# AD_DA.net
KiCad netlist of a schematic drawn in Altium Designer
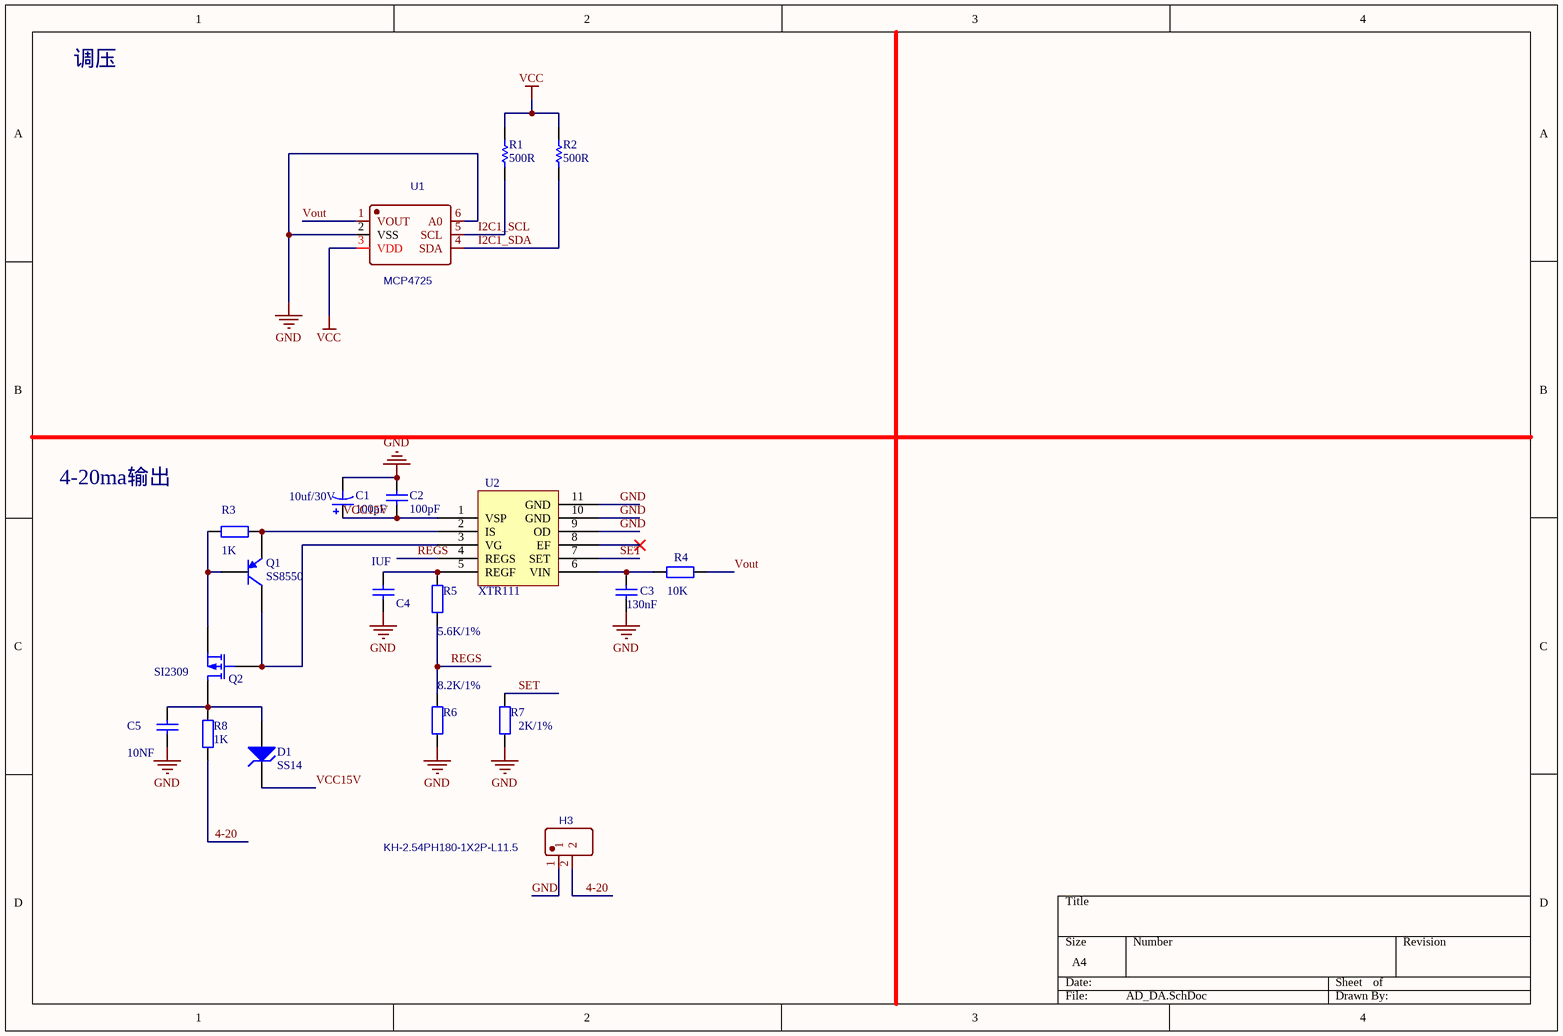
[diagram p0: AD_DA.SchDoc]

(export (version "E")
  (design (tool "Eeschema 10.0.6"))
  (components
    (comp (ref "C1")
      (value "10uf/30V")
      (footprint "RB7.6-15")
      (description "Polarized Capacitor (Radial)")
      (fields (field (name "ALTIUM_VALUE") "100pF") (field (name "PUBLISHER") "Altium Limited"))
      (libsource (lib "Miscellaneous Devices") (part "Cap Pol1"))
    )
    (comp (ref "C2")
      (value "100pF")
      (footprint "RAD-0.3")
      (description "Capacitor")
      (fields (field (name "Comment") "104") (field (name "PUBLISHER") "Altium Limited"))
      (libsource (lib "Miscellaneous Devices") (part "Cap"))
    )
    (comp (ref "C3")
      (value "130nF")
      (footprint "0603")
      (description "Capacitor")
      (libsource (lib "MyStandardSchLib") (part "Cap Smd"))
    )
    (comp (ref "C4")
      (value "IUF")
      (footprint "RAD-0.3")
      (description "Capacitor")
      (fields (field (name "PUBLISHER") "Altium Limited"))
      (libsource (lib "Miscellaneous Devices") (part "Cap"))
    )
    (comp (ref "C5")
      (value "10NF")
      (footprint "RAD-0.3")
      (description "Capacitor")
      (fields (field (name "PUBLISHER") "Altium Limited"))
      (libsource (lib "Miscellaneous Devices") (part "Cap"))
    )
    (comp (ref "D1")
      (value "SS14")
      (footprint "DIODE-0.7")
      (description "Zener Diode")
      (fields (field (name "PUBLISHER") "Altium Limited"))
      (libsource (lib "Miscellaneous Devices") (part "D Zener"))
    )
    (comp (ref "H3")
      (value "KH-2.54PH180-1X2P-L11.5")
      (footprint "1*2P")
      (fields
        (field (name "BOM_SUPPLIER PART") "C2905435")
        (field (name "BOM_MANUFACTURER PART") "KH-2.54PH180-1X4P-L11.5")
        (field (name "CONTRIBUTOR") "LCSC")
      )
      (libsource (lib "4_20MA_I2C") (part "KH-2.54PH180-1X2P-L11.5"))
    )
    (comp (ref "Q1")
      (value "SS8550")
      (footprint "SOT-23B_N")
      (description "PNP Bipolar Transistor")
      (fields (field (name "PUBLISHER") "Altium Limited"))
      (libsource (lib "Miscellaneous Devices") (part "PNP"))
    )
    (comp (ref "Q2")
      (value "SI2309")
      (footprint "E3")
      (description "P-Channel MOSFET")
      (fields (field (name "PUBLISHER") "Altium Limited"))
      (libsource (lib "Miscellaneous Devices") (part "MOSFET-P"))
    )
    (comp (ref "R1")
      (value "500R")
      (footprint "0805R")
      (description "Resistor")
      (fields (field (name "PUBLISHER") "Altium Limited"))
      (libsource (lib "WarShip_ExtraBoard") (part "RES"))
    )
    (comp (ref "R2")
      (value "500R")
      (footprint "0805R")
      (description "Resistor")
      (fields (field (name "PUBLISHER") "Altium Limited"))
      (libsource (lib "WarShip_ExtraBoard") (part "RES"))
    )
    (comp (ref "R3")
      (value "1K")
      (footprint "0603_R")
      (description "Resistor")
      (fields (field (name "Comment") "15R") (field (name "PUBLISHER") "Altium Limited"))
      (libsource (lib "") (part "Res2_3"))
    )
    (comp (ref "R4")
      (value "10K")
      (footprint "0603_R")
      (description "Resistor")
      (fields (field (name "PUBLISHER") "Altium Limited"))
      (libsource (lib "") (part "Res2_2"))
    )
    (comp (ref "R5")
      (value "5.6K/1%")
      (footprint "0603_R")
      (description "Resistor")
      (fields (field (name "PUBLISHER") "Altium Limited"))
      (libsource (lib "Miscellaneous Devices") (part "Res2"))
    )
    (comp (ref "R6")
      (value "8.2K/1%")
      (footprint "0603_R")
      (description "Resistor")
      (fields (field (name "PUBLISHER") "Altium Limited"))
      (libsource (lib "Miscellaneous Devices") (part "Res2"))
    )
    (comp (ref "R7")
      (value "2K/1%")
      (footprint "0603_R")
      (description "Resistor")
      (fields (field (name "PUBLISHER") "Altium Limited"))
      (libsource (lib "") (part "Res2_1"))
    )
    (comp (ref "R8")
      (value "1K")
      (footprint "0603_R")
      (description "Resistor")
      (fields (field (name "Comment") "15R") (field (name "PUBLISHER") "Altium Limited"))
      (libsource (lib "Miscellaneous Devices") (part "Res2"))
    )
    (comp (ref "U1")
      (value "MCP4725")
      (footprint "MCP4725")
      (fields
        (field (name "BOM_MANUFACTURER PART") "MCP4725A0T-E/CH")
        (field (name "BOM_SUPPLIER PART") "C144198")
        (field (name "CONTRIBUTOR") "LCSC")
      )
      (libsource (lib "4_20MA_I2C") (part "MCP4725A0T-E/CH"))
    )
    (comp (ref "U2") (value "XTR111") (footprint "XTR111") (libsource (lib "XTR111") (part "XTR111")))
  )
  (nets
    (net (code "1") (name "/4-20") (class "Default")
      (node (ref "H3") (pin "2") (pinfunction "2_2") (pintype "passive"))
      (node (ref "R8") (pin "2") (pinfunction "2_2") (pintype "passive"))
    )
    (net (code "2") (name "/I2C1_SCL") (class "Default")
      (node (ref "R1") (pin "1") (pinfunction "1_1") (pintype "passive"))
      (node (ref "U1") (pin "5") (pinfunction "SCL_5") (pintype "passive"))
    )
    (net (code "3") (name "/I2C1_SDA") (class "Default")
      (node (ref "R2") (pin "1") (pinfunction "1_1") (pintype "passive"))
      (node (ref "U1") (pin "4") (pinfunction "SDA_4") (pintype "passive"))
    )
    (net (code "4") (name "/REGS") (class "Default")
      (node (ref "R5") (pin "2") (pinfunction "2_2") (pintype "passive"))
      (node (ref "R6") (pin "1") (pinfunction "1_1") (pintype "passive"))
      (node (ref "U2") (pin "4") (pinfunction "REGS_4") (pintype "passive"))
    )
    (net (code "5") (name "/SET") (class "Default")
      (node (ref "R7") (pin "2") (pinfunction "2_2") (pintype "passive"))
      (node (ref "U2") (pin "7") (pinfunction "SET_7") (pintype "passive"))
    )
    (net (code "6") (name "/VCC15V") (class "Default")
      (node (ref "C1") (pin "1") (pinfunction "1_1") (pintype "passive"))
      (node (ref "C2") (pin "2") (pinfunction "2_2") (pintype "passive"))
      (node (ref "D1") (pin "2") (pinfunction "K_2") (pintype "passive"))
      (node (ref "U2") (pin "1") (pinfunction "VSP_1") (pintype "passive"))
    )
    (net (code "7") (name "/Vout") (class "Default")
      (node (ref "R4") (pin "2") (pinfunction "2_2") (pintype "passive"))
      (node (ref "U1") (pin "1") (pinfunction "VOUT_1") (pintype "passive"))
    )
    (net (code "8") (name "GND") (class "Default")
      (node (ref "C1") (pin "2") (pinfunction "2_2") (pintype "passive"))
      (node (ref "C2") (pin "1") (pinfunction "1_1") (pintype "passive"))
      (node (ref "C3") (pin "2") (pinfunction "2_2") (pintype "passive"))
      (node (ref "C4") (pin "1") (pinfunction "1_1") (pintype "passive"))
      (node (ref "C5") (pin "2") (pinfunction "2_2") (pintype "passive"))
      (node (ref "H3") (pin "1") (pinfunction "1_1") (pintype "passive"))
      (node (ref "R6") (pin "2") (pinfunction "2_2") (pintype "passive"))
      (node (ref "R7") (pin "1") (pinfunction "1_1") (pintype "passive"))
      (node (ref "U1") (pin "2") (pinfunction "VSS_2") (pintype "passive"))
      (node (ref "U1") (pin "6") (pinfunction "A0_6") (pintype "passive"))
      (node (ref "U2") (pin "10") (pinfunction "GND_10") (pintype "passive"))
      (node (ref "U2") (pin "11") (pinfunction "GND_11") (pintype "passive"))
      (node (ref "U2") (pin "9") (pinfunction "OD_9") (pintype "passive"))
    )
    (net (code "9") (name "Net-(D1-A)") (class "Default")
      (node (ref "C5") (pin "1") (pinfunction "1_1") (pintype "passive"))
      (node (ref "D1") (pin "1") (pinfunction "A_1") (pintype "passive"))
      (node (ref "Q2") (pin "1") (pinfunction "D_1") (pintype "passive"))
      (node (ref "R8") (pin "1") (pinfunction "1_1") (pintype "passive"))
    )
    (net (code "10") (name "Net-(Q1-B)") (class "Default")
      (node (ref "Q1") (pin "2") (pinfunction "B_2") (pintype "passive"))
      (node (ref "Q2") (pin "3") (pinfunction "S_3") (pintype "passive"))
      (node (ref "R3") (pin "2") (pinfunction "2_2") (pintype "passive"))
    )
    (net (code "11") (name "Net-(Q1-C)") (class "Default")
      (node (ref "Q1") (pin "1") (pinfunction "C_1") (pintype "passive"))
      (node (ref "Q2") (pin "2") (pinfunction "G_2") (pintype "passive"))
      (node (ref "U2") (pin "3") (pinfunction "VG_3") (pintype "passive"))
    )
    (net (code "12") (name "Net-(Q1-E)") (class "Default")
      (node (ref "Q1") (pin "3") (pinfunction "E_3") (pintype "passive"))
      (node (ref "R3") (pin "1") (pinfunction "1_1") (pintype "passive"))
      (node (ref "U2") (pin "2") (pinfunction "IS_2") (pintype "passive"))
    )
    (net (code "13") (name "Net-(U2-REGF)") (class "Default")
      (node (ref "C4") (pin "2") (pinfunction "2_2") (pintype "passive"))
      (node (ref "R5") (pin "1") (pinfunction "1_1") (pintype "passive"))
      (node (ref "U2") (pin "5") (pinfunction "REGF_5") (pintype "passive"))
    )
    (net (code "14") (name "Net-(U2-VIN)") (class "Default")
      (node (ref "C3") (pin "1") (pinfunction "1_1") (pintype "passive"))
      (node (ref "R4") (pin "1") (pinfunction "1_1") (pintype "passive"))
      (node (ref "U2") (pin "6") (pinfunction "VIN_6") (pintype "passive"))
    )
    (net (code "15") (name "VCC") (class "Default")
      (node (ref "R1") (pin "2") (pinfunction "2_2") (pintype "passive"))
      (node (ref "R2") (pin "2") (pinfunction "2_2") (pintype "passive"))
      (node (ref "U1") (pin "3") (pinfunction "VDD_3") (pintype "passive"))
    )
    (net (code "16") (name "unconnected-(U2-EF-Pad8)") (class "Default")
      (node (ref "U2") (pin "8") (pinfunction "EF_8") (pintype "passive+no_connect"))
    )
  )
)
